# imu_68.net
KiCad netlist of a schematic drawn in EAGLE
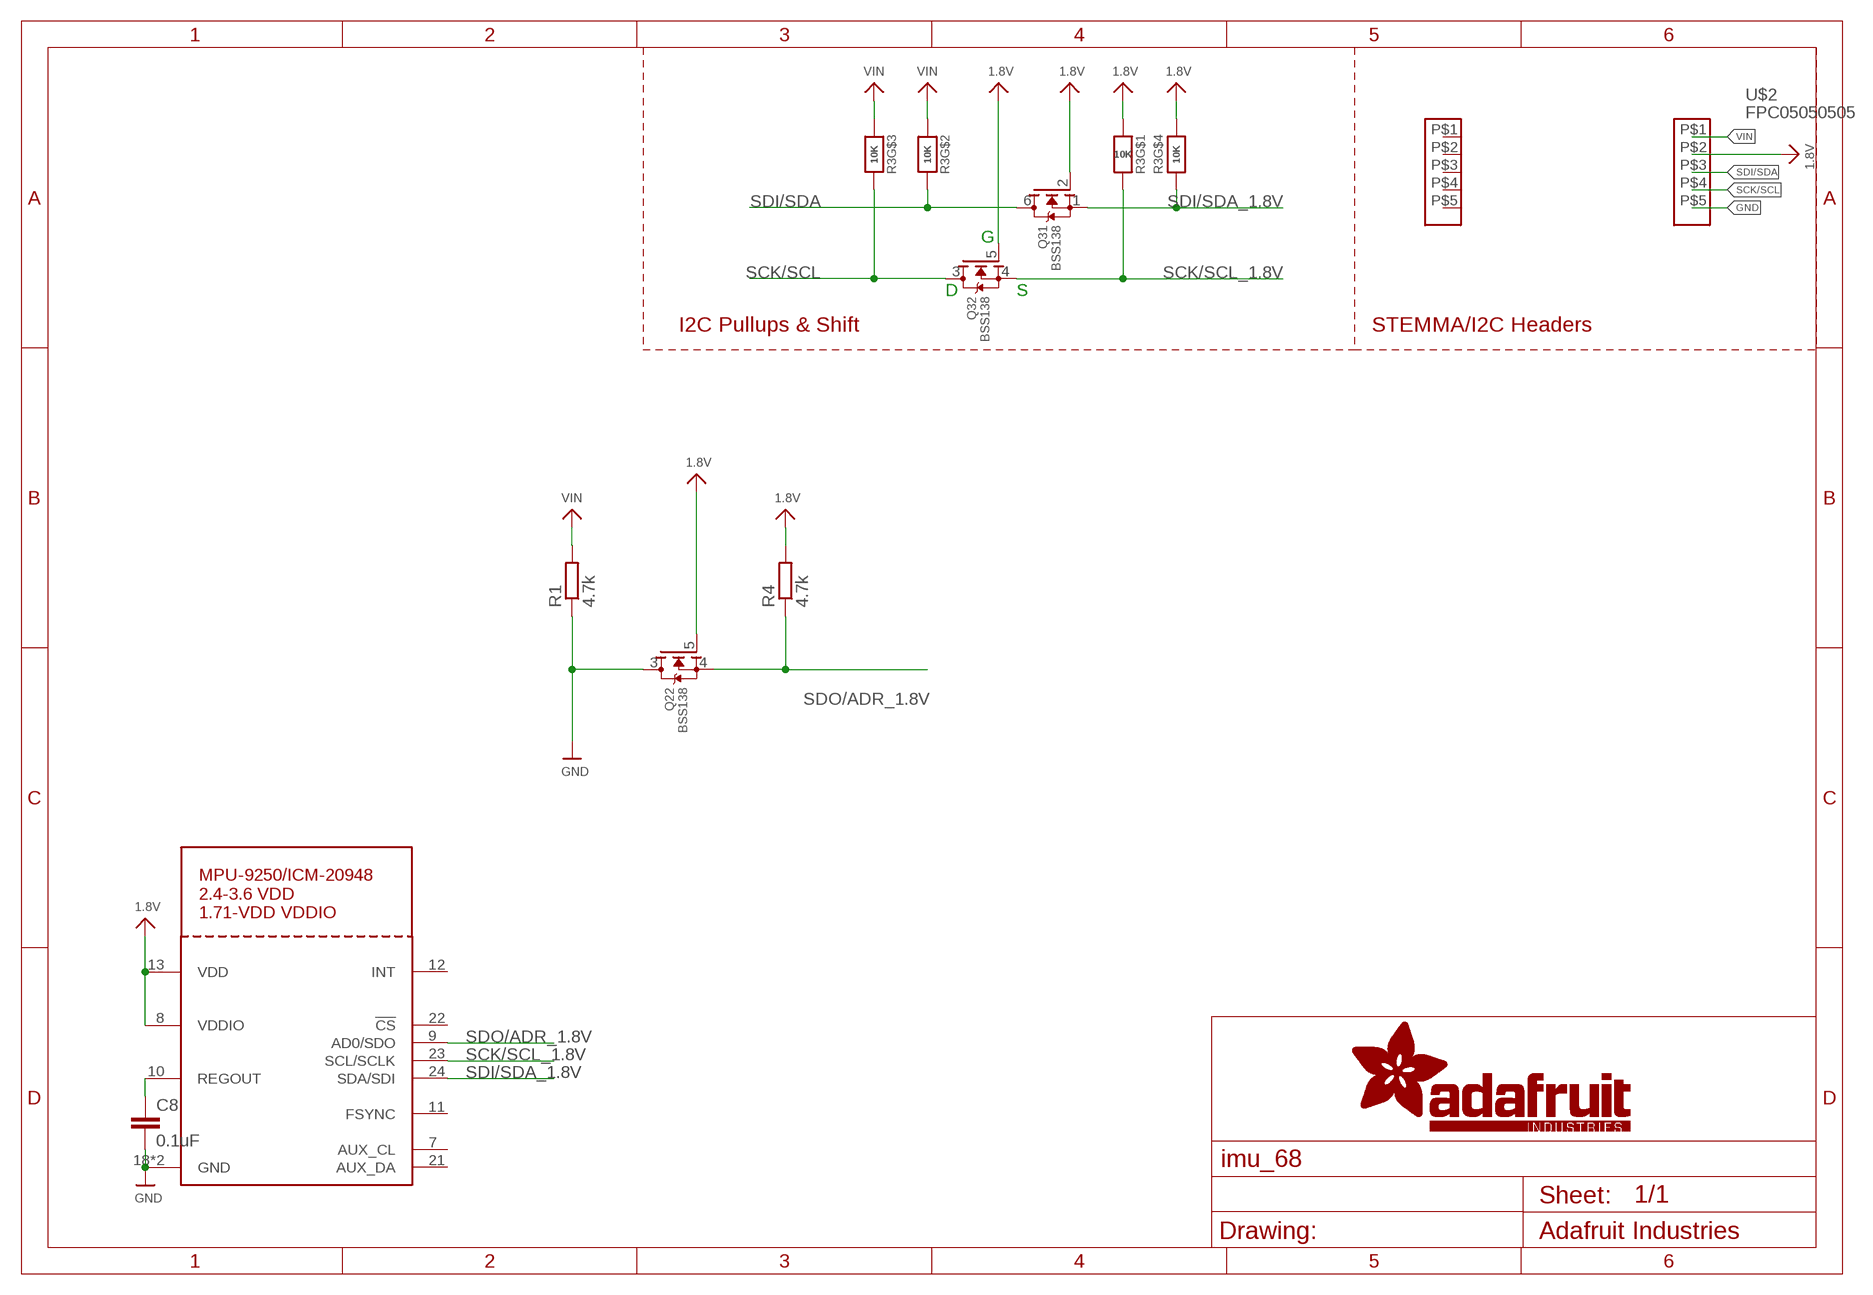
[diagram p0: schematic, sheet 1]

(export (version "E")
  (design (tool "Eeschema 10.0.6"))
  (components
    (comp (ref "C8")
      (value "0.1uF")
      (footprint "eagle-import:C0201")
      (libsource (lib "eagle-import") (part "C-EUC0201"))
    )
    (comp (ref "Q2")
      (value "BSS138")
      (footprint "eagle-import:SOT363")
      (libsource (lib "eagle-import") (part "MOSFET-N_DUAL"))
    )
    (comp (ref "Q3")
      (value "BSS138")
      (footprint "eagle-import:SOT363")
      (libsource (lib "eagle-import") (part "MOSFET-N_DUAL"))
    )
    (comp (ref "R1")
      (value "4.7k")
      (footprint "eagle-import:R0402")
      (libsource (lib "eagle-import") (part "R-EU_R0402"))
    )
    (comp (ref "R3")
      (value "10K")
      (footprint "eagle-import:RESPACK_4X0603")
      (libsource (lib "eagle-import") (part "RESISTOR_4PACK"))
    )
    (comp (ref "R4")
      (value "4.7k")
      (footprint "eagle-import:R0402")
      (libsource (lib "eagle-import") (part "R-EU_R0402"))
    )
    (comp (ref "U$1")
      (value "FPC05050505")
      (footprint "eagle-import:FPB0505")
      (libsource (lib "eagle-import") (part "FPC05050505"))
    )
    (comp (ref "U$2")
      (value "FPC05050505")
      (footprint "eagle-import:FPB0505")
      (libsource (lib "eagle-import") (part "FPC05050505"))
    )
    (comp (ref "U$21")
      (value "MPU-9250_ICM20948")
      (footprint "eagle-import:QFN24_3MM_NOEP")
      (libsource (lib "eagle-import") (part "MPU-9250_ICM20948"))
    )
  )
  (nets
    (net (code "1") (name "/SCK{slash}SCL_1.8V") (class "Default")
      (node (ref "Q3") (pin "4") (pinfunction "S_4") (pintype "bidirectional"))
      (node (ref "R3") (pin "1") (pinfunction "1_1") (pintype "passive"))
      (node (ref "U$21") (pin "23") (pinfunction "SCL/SCLK_23") (pintype "bidirectional"))
    )
    (net (code "2") (name "/SDI{slash}SDA_1.8V") (class "Default")
      (node (ref "Q3") (pin "1") (pinfunction "S_1") (pintype "bidirectional"))
      (node (ref "R3") (pin "5") (pinfunction "2_5") (pintype "passive"))
      (node (ref "U$21") (pin "24") (pinfunction "SDA/SDI_24") (pintype "bidirectional"))
    )
    (net (code "3") (name "/SDO{slash}ADR_1.8V") (class "Default")
      (node (ref "Q2") (pin "4") (pinfunction "S_4") (pintype "bidirectional"))
      (node (ref "R4") (pin "1") (pinfunction "1_1") (pintype "passive"))
      (node (ref "U$21") (pin "9") (pinfunction "AD0/SDO_9") (pintype "bidirectional"))
    )
    (net (code "4") (name "1.8V") (class "Default")
      (node (ref "Q2") (pin "5") (pinfunction "G_5") (pintype "bidirectional"))
      (node (ref "Q3") (pin "2") (pinfunction "G_2") (pintype "bidirectional"))
      (node (ref "Q3") (pin "5") (pinfunction "G_5") (pintype "bidirectional"))
      (node (ref "R3") (pin "4") (pinfunction "1_4") (pintype "passive"))
      (node (ref "R3") (pin "8") (pinfunction "2_8") (pintype "passive"))
      (node (ref "R4") (pin "2") (pinfunction "2_2") (pintype "passive"))
      (node (ref "U$2") (pin "P$2") (pinfunction "P$2_P$2") (pintype "bidirectional"))
      (node (ref "U$21") (pin "13") (pinfunction "VDD_13") (pintype "bidirectional"))
      (node (ref "U$21") (pin "8") (pinfunction "VDDIO_8") (pintype "bidirectional"))
    )
    (net (code "5") (name "GND") (class "Default")
      (node (ref "C8") (pin "2") (pinfunction "2_2") (pintype "passive"))
      (node (ref "Q2") (pin "3") (pinfunction "D_3") (pintype "bidirectional"))
      (node (ref "R1") (pin "1") (pinfunction "1_1") (pintype "passive"))
      (node (ref "U$2") (pin "P$5") (pinfunction "P$5_P$5") (pintype "bidirectional"))
      (node (ref "U$21") (pin "18") (pinfunction "GND_18") (pintype "bidirectional"))
      (node (ref "U$21") (pin "20") (pinfunction "GND_20") (pintype "bidirectional"))
    )
    (net (code "6") (name "Net-(U$21-REGOUT)") (class "Default")
      (node (ref "C8") (pin "1") (pinfunction "1_1") (pintype "passive"))
      (node (ref "U$21") (pin "10") (pinfunction "REGOUT_10") (pintype "bidirectional"))
    )
    (net (code "7") (name "SCK{slash}SCL") (class "Default")
      (node (ref "Q3") (pin "3") (pinfunction "D_3") (pintype "bidirectional"))
      (node (ref "R3") (pin "6") (pinfunction "2_6") (pintype "passive"))
      (node (ref "U$2") (pin "P$4") (pinfunction "P$4_P$4") (pintype "bidirectional"))
    )
    (net (code "8") (name "SDI{slash}SDA") (class "Default")
      (node (ref "Q3") (pin "6") (pinfunction "D_6") (pintype "bidirectional"))
      (node (ref "R3") (pin "7") (pinfunction "2_7") (pintype "passive"))
      (node (ref "U$2") (pin "P$3") (pinfunction "P$3_P$3") (pintype "bidirectional"))
    )
    (net (code "9") (name "VIN") (class "Default")
      (node (ref "R1") (pin "2") (pinfunction "2_2") (pintype "passive"))
      (node (ref "R3") (pin "2") (pinfunction "1_2") (pintype "passive"))
      (node (ref "R3") (pin "3") (pinfunction "1_3") (pintype "passive"))
      (node (ref "U$2") (pin "P$1") (pinfunction "P$1_P$1") (pintype "bidirectional"))
    )
    (net (code "10") (name "unconnected-(U$1-PadP$1)") (class "Default")
      (node (ref "U$1") (pin "P$1") (pinfunction "P$1_P$1") (pintype "bidirectional"))
    )
    (net (code "11") (name "unconnected-(U$1-PadP$2)") (class "Default")
      (node (ref "U$1") (pin "P$2") (pinfunction "P$2_P$2") (pintype "bidirectional"))
    )
    (net (code "12") (name "unconnected-(U$1-PadP$3)") (class "Default")
      (node (ref "U$1") (pin "P$3") (pinfunction "P$3_P$3") (pintype "bidirectional"))
    )
    (net (code "13") (name "unconnected-(U$1-PadP$4)") (class "Default")
      (node (ref "U$1") (pin "P$4") (pinfunction "P$4_P$4") (pintype "bidirectional"))
    )
    (net (code "14") (name "unconnected-(U$1-PadP$5)") (class "Default")
      (node (ref "U$1") (pin "P$5") (pinfunction "P$5_P$5") (pintype "bidirectional"))
    )
    (net (code "15") (name "unconnected-(U$21-AUX_CL-Pad7)") (class "Default")
      (node (ref "U$21") (pin "7") (pinfunction "AUX_CL_7") (pintype "bidirectional"))
    )
    (net (code "16") (name "unconnected-(U$21-AUX_DA-Pad21)") (class "Default")
      (node (ref "U$21") (pin "21") (pinfunction "AUX_DA_21") (pintype "bidirectional"))
    )
    (net (code "17") (name "unconnected-(U$21-FSYNC-Pad11)") (class "Default")
      (node (ref "U$21") (pin "11") (pinfunction "FSYNC_11") (pintype "bidirectional"))
    )
    (net (code "18") (name "unconnected-(U$21-INT-Pad12)") (class "Default")
      (node (ref "U$21") (pin "12") (pinfunction "INT_12") (pintype "bidirectional"))
    )
    (net (code "19") (name "unconnected-(U$21-~{CS}-Pad22)") (class "Default")
      (node (ref "U$21") (pin "22") (pinfunction "~{CS}_22") (pintype "bidirectional"))
    )
  )
)
